# rfm12.net
KiCad netlist of a schematic drawn in EAGLE
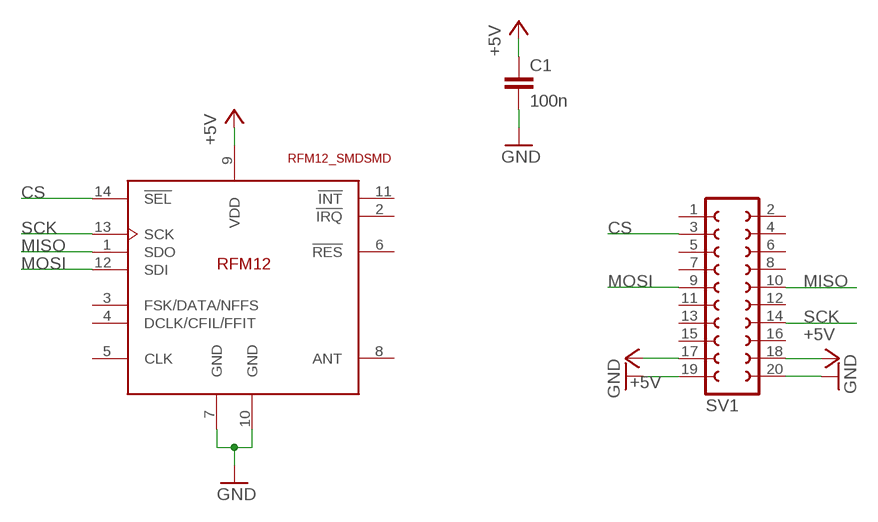
[diagram p0: schematic, sheet 1]

(export (version "E")
  (design (tool "Eeschema 10.0.6"))
  (components
    (comp (ref "C1")
      (value "100n")
      (footprint "eagle-import:C0805")
      (libsource (lib "eagle-import") (part "C-EUC0805"))
    )
    (comp (ref "SV1")
      (value "FE10-2")
      (footprint "eagle-import:FE10-2")
      (libsource (lib "eagle-import") (part "FE10-2"))
    )
    (comp (ref "U$1")
      (value "RFM12_SMDSMD")
      (footprint "eagle-import:RFM12")
      (libsource (lib "eagle-import") (part "RFM12_SMDSMD"))
    )
  )
  (nets
    (net (code "1") (name "+5V") (class "Default")
      (node (ref "C1") (pin "1") (pinfunction "1_1") (pintype "passive"))
      (node (ref "SV1") (pin "17") (pinfunction "17_17") (pintype "passive"))
      (node (ref "SV1") (pin "18") (pinfunction "18_18") (pintype "passive"))
      (node (ref "U$1") (pin "9") (pinfunction "VDD_9") (pintype "power_in"))
    )
    (net (code "2") (name "/CS") (class "Default")
      (node (ref "SV1") (pin "3") (pinfunction "3_3") (pintype "passive"))
      (node (ref "U$1") (pin "14") (pinfunction "~{SEL}_14") (pintype "input"))
    )
    (net (code "3") (name "/MISO") (class "Default")
      (node (ref "SV1") (pin "10") (pinfunction "10_10") (pintype "passive"))
      (node (ref "U$1") (pin "1") (pinfunction "SDO_1") (pintype "output"))
    )
    (net (code "4") (name "/MOSI") (class "Default")
      (node (ref "SV1") (pin "9") (pinfunction "9_9") (pintype "passive"))
      (node (ref "U$1") (pin "12") (pinfunction "SDI_12") (pintype "input"))
    )
    (net (code "5") (name "/SCK") (class "Default")
      (node (ref "SV1") (pin "14") (pinfunction "14_14") (pintype "passive"))
      (node (ref "U$1") (pin "13") (pinfunction "SCK_13") (pintype "input"))
    )
    (net (code "6") (name "GND") (class "Default")
      (node (ref "C1") (pin "2") (pinfunction "2_2") (pintype "passive"))
      (node (ref "SV1") (pin "19") (pinfunction "19_19") (pintype "passive"))
      (node (ref "SV1") (pin "20") (pinfunction "20_20") (pintype "passive"))
      (node (ref "U$1") (pin "10") (pinfunction "GND_10") (pintype "passive"))
      (node (ref "U$1") (pin "7") (pinfunction "GND_7") (pintype "passive"))
    )
    (net (code "7") (name "unconnected-(SV1-Pad1)") (class "Default")
      (node (ref "SV1") (pin "1") (pinfunction "1_1") (pintype "passive"))
    )
    (net (code "8") (name "unconnected-(SV1-Pad2)") (class "Default")
      (node (ref "SV1") (pin "2") (pinfunction "2_2") (pintype "passive"))
    )
    (net (code "9") (name "unconnected-(SV1-Pad4)") (class "Default")
      (node (ref "SV1") (pin "4") (pinfunction "4_4") (pintype "passive"))
    )
    (net (code "10") (name "unconnected-(SV1-Pad5)") (class "Default")
      (node (ref "SV1") (pin "5") (pinfunction "5_5") (pintype "passive"))
    )
    (net (code "11") (name "unconnected-(SV1-Pad6)") (class "Default")
      (node (ref "SV1") (pin "6") (pinfunction "6_6") (pintype "passive"))
    )
    (net (code "12") (name "unconnected-(SV1-Pad7)") (class "Default")
      (node (ref "SV1") (pin "7") (pinfunction "7_7") (pintype "passive"))
    )
    (net (code "13") (name "unconnected-(SV1-Pad8)") (class "Default")
      (node (ref "SV1") (pin "8") (pinfunction "8_8") (pintype "passive"))
    )
    (net (code "14") (name "unconnected-(SV1-Pad11)") (class "Default")
      (node (ref "SV1") (pin "11") (pinfunction "11_11") (pintype "passive"))
    )
    (net (code "15") (name "unconnected-(SV1-Pad12)") (class "Default")
      (node (ref "SV1") (pin "12") (pinfunction "12_12") (pintype "passive"))
    )
    (net (code "16") (name "unconnected-(SV1-Pad13)") (class "Default")
      (node (ref "SV1") (pin "13") (pinfunction "13_13") (pintype "passive"))
    )
    (net (code "17") (name "unconnected-(SV1-Pad15)") (class "Default")
      (node (ref "SV1") (pin "15") (pinfunction "15_15") (pintype "passive"))
    )
    (net (code "18") (name "unconnected-(SV1-Pad16)") (class "Default")
      (node (ref "SV1") (pin "16") (pinfunction "16_16") (pintype "passive"))
    )
    (net (code "19") (name "unconnected-(U$1-ANT-Pad8)") (class "Default")
      (node (ref "U$1") (pin "8") (pinfunction "ANT_8") (pintype "bidirectional"))
    )
    (net (code "20") (name "unconnected-(U$1-CLK-Pad5)") (class "Default")
      (node (ref "U$1") (pin "5") (pinfunction "CLK_5") (pintype "output"))
    )
    (net (code "21") (name "unconnected-(U$1-DCLK{slash}CFIL{slash}FFIT-Pad4)") (class "Default")
      (node (ref "U$1") (pin "4") (pinfunction "DCLK/CFIL/FFIT_4") (pintype "bidirectional"))
    )
    (net (code "22") (name "unconnected-(U$1-FSK{slash}DATA{slash}NFFS-Pad3)") (class "Default")
      (node (ref "U$1") (pin "3") (pinfunction "FSK/DATA/NFFS_3") (pintype "bidirectional"))
    )
    (net (code "23") (name "unconnected-(U$1-~{INT}-Pad11)") (class "Default")
      (node (ref "U$1") (pin "11") (pinfunction "~{INT}_11") (pintype "bidirectional"))
    )
    (net (code "24") (name "unconnected-(U$1-~{IRQ}-Pad2)") (class "Default")
      (node (ref "U$1") (pin "2") (pinfunction "~{IRQ}_2") (pintype "output"))
    )
    (net (code "25") (name "unconnected-(U$1-~{RES}-Pad6)") (class "Default")
      (node (ref "U$1") (pin "6") (pinfunction "~{RES}_6") (pintype "bidirectional"))
    )
  )
)
